# EIB32-JAE-HPC-v1.net
KiCad netlist of a schematic drawn in EAGLE
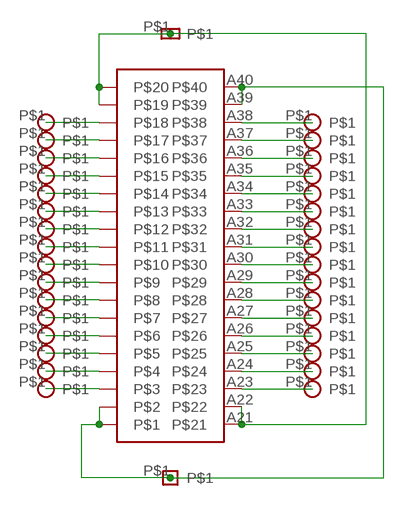
[diagram p0: schematic, sheet 1]

(export (version "E")
  (design (tool "Eeschema 10.0.6"))
  (components
    (comp (ref "U$1")
      (value "WR-40SB-VFH30")
      (footprint "eagle-import:WR-40SB-VFH30")
      (libsource (lib "eagle-import") (part "WR-40SB-VFH30"))
    )
    (comp (ref "U$2")
      (value "EIB-GND-HOLE-PAD-SMALL")
      (footprint "eagle-import:EIB-GND-HOLE-PAD-SMALL")
      (libsource (lib "eagle-import") (part "EIB-GND-HOLE-PAD-SMALL"))
    )
    (comp (ref "U$3")
      (value "EIB-GND-HOLE-PAD")
      (footprint "eagle-import:EIB-GND-HOLE-PAD")
      (libsource (lib "eagle-import") (part "EIB-GND-HOLE-PAD"))
    )
    (comp (ref "U$5")
      (value "EIB-TETRODE-HOLE-RS-PAD")
      (footprint "eagle-import:EIB-TETRODE-HOLE-RS-PAD")
      (libsource (lib "eagle-import") (part "EIB-TETRODE-HOLE-RS-PAD"))
    )
    (comp (ref "U$6")
      (value "EIB-TETRODE-HOLE-RS-PAD")
      (footprint "eagle-import:EIB-TETRODE-HOLE-RS-PAD")
      (libsource (lib "eagle-import") (part "EIB-TETRODE-HOLE-RS-PAD"))
    )
    (comp (ref "U$7")
      (value "EIB-TETRODE-HOLE-RS-PAD")
      (footprint "eagle-import:EIB-TETRODE-HOLE-RS-PAD")
      (libsource (lib "eagle-import") (part "EIB-TETRODE-HOLE-RS-PAD"))
    )
    (comp (ref "U$8")
      (value "EIB-TETRODE-HOLE-RS-PAD")
      (footprint "eagle-import:EIB-TETRODE-HOLE-RS-PAD")
      (libsource (lib "eagle-import") (part "EIB-TETRODE-HOLE-RS-PAD"))
    )
    (comp (ref "U$9")
      (value "EIB-TETRODE-HOLE-RS-PAD")
      (footprint "eagle-import:EIB-TETRODE-HOLE-RS-PAD")
      (libsource (lib "eagle-import") (part "EIB-TETRODE-HOLE-RS-PAD"))
    )
    (comp (ref "U$10")
      (value "EIB-TETRODE-HOLE-RS-PAD")
      (footprint "eagle-import:EIB-TETRODE-HOLE-RS-PAD")
      (libsource (lib "eagle-import") (part "EIB-TETRODE-HOLE-RS-PAD"))
    )
    (comp (ref "U$11")
      (value "EIB-TETRODE-HOLE-RS-PAD")
      (footprint "eagle-import:EIB-TETRODE-HOLE-RS-PAD")
      (libsource (lib "eagle-import") (part "EIB-TETRODE-HOLE-RS-PAD"))
    )
    (comp (ref "U$12")
      (value "EIB-TETRODE-HOLE-RS-PAD")
      (footprint "eagle-import:EIB-TETRODE-HOLE-RS-PAD")
      (libsource (lib "eagle-import") (part "EIB-TETRODE-HOLE-RS-PAD"))
    )
    (comp (ref "U$13")
      (value "EIB-TETRODE-HOLE-RS-PAD")
      (footprint "eagle-import:EIB-TETRODE-HOLE-RS-PAD")
      (libsource (lib "eagle-import") (part "EIB-TETRODE-HOLE-RS-PAD"))
    )
    (comp (ref "U$14")
      (value "EIB-TETRODE-HOLE-RS-PAD")
      (footprint "eagle-import:EIB-TETRODE-HOLE-RS-PAD")
      (libsource (lib "eagle-import") (part "EIB-TETRODE-HOLE-RS-PAD"))
    )
    (comp (ref "U$15")
      (value "EIB-TETRODE-HOLE-RS-PAD")
      (footprint "eagle-import:EIB-TETRODE-HOLE-RS-PAD")
      (libsource (lib "eagle-import") (part "EIB-TETRODE-HOLE-RS-PAD"))
    )
    (comp (ref "U$16")
      (value "EIB-TETRODE-HOLE-RS-PAD")
      (footprint "eagle-import:EIB-TETRODE-HOLE-RS-PAD")
      (libsource (lib "eagle-import") (part "EIB-TETRODE-HOLE-RS-PAD"))
    )
    (comp (ref "U$17")
      (value "EIB-TETRODE-HOLE-RS-PAD")
      (footprint "eagle-import:EIB-TETRODE-HOLE-RS-PAD")
      (libsource (lib "eagle-import") (part "EIB-TETRODE-HOLE-RS-PAD"))
    )
    (comp (ref "U$18")
      (value "EIB-TETRODE-HOLE-RS-PAD")
      (footprint "eagle-import:EIB-TETRODE-HOLE-RS-PAD")
      (libsource (lib "eagle-import") (part "EIB-TETRODE-HOLE-RS-PAD"))
    )
    (comp (ref "U$19")
      (value "EIB-TETRODE-HOLE-RS-PAD")
      (footprint "eagle-import:EIB-TETRODE-HOLE-RS-PAD")
      (libsource (lib "eagle-import") (part "EIB-TETRODE-HOLE-RS-PAD"))
    )
    (comp (ref "U$20")
      (value "EIB-TETRODE-HOLE-RS-PAD")
      (footprint "eagle-import:EIB-TETRODE-HOLE-RS-PAD")
      (libsource (lib "eagle-import") (part "EIB-TETRODE-HOLE-RS-PAD"))
    )
    (comp (ref "U$23")
      (value "EIB-TETRODE-HOLE-RS-PAD")
      (footprint "eagle-import:EIB-TETRODE-HOLE-RS-PAD")
      (libsource (lib "eagle-import") (part "EIB-TETRODE-HOLE-RS-PAD"))
    )
    (comp (ref "U$24")
      (value "EIB-TETRODE-HOLE-RS-PAD")
      (footprint "eagle-import:EIB-TETRODE-HOLE-RS-PAD")
      (libsource (lib "eagle-import") (part "EIB-TETRODE-HOLE-RS-PAD"))
    )
    (comp (ref "U$25")
      (value "EIB-TETRODE-HOLE-RS-PAD")
      (footprint "eagle-import:EIB-TETRODE-HOLE-RS-PAD")
      (libsource (lib "eagle-import") (part "EIB-TETRODE-HOLE-RS-PAD"))
    )
    (comp (ref "U$26")
      (value "EIB-TETRODE-HOLE-RS-PAD")
      (footprint "eagle-import:EIB-TETRODE-HOLE-RS-PAD")
      (libsource (lib "eagle-import") (part "EIB-TETRODE-HOLE-RS-PAD"))
    )
    (comp (ref "U$27")
      (value "EIB-TETRODE-HOLE-RS-PAD")
      (footprint "eagle-import:EIB-TETRODE-HOLE-RS-PAD")
      (libsource (lib "eagle-import") (part "EIB-TETRODE-HOLE-RS-PAD"))
    )
    (comp (ref "U$28")
      (value "EIB-TETRODE-HOLE-RS-PAD")
      (footprint "eagle-import:EIB-TETRODE-HOLE-RS-PAD")
      (libsource (lib "eagle-import") (part "EIB-TETRODE-HOLE-RS-PAD"))
    )
    (comp (ref "U$29")
      (value "EIB-TETRODE-HOLE-RS-PAD")
      (footprint "eagle-import:EIB-TETRODE-HOLE-RS-PAD")
      (libsource (lib "eagle-import") (part "EIB-TETRODE-HOLE-RS-PAD"))
    )
    (comp (ref "U$30")
      (value "EIB-TETRODE-HOLE-RS-PAD")
      (footprint "eagle-import:EIB-TETRODE-HOLE-RS-PAD")
      (libsource (lib "eagle-import") (part "EIB-TETRODE-HOLE-RS-PAD"))
    )
    (comp (ref "U$31")
      (value "EIB-TETRODE-HOLE-RS-PAD")
      (footprint "eagle-import:EIB-TETRODE-HOLE-RS-PAD")
      (libsource (lib "eagle-import") (part "EIB-TETRODE-HOLE-RS-PAD"))
    )
    (comp (ref "U$32")
      (value "EIB-TETRODE-HOLE-RS-PAD")
      (footprint "eagle-import:EIB-TETRODE-HOLE-RS-PAD")
      (libsource (lib "eagle-import") (part "EIB-TETRODE-HOLE-RS-PAD"))
    )
    (comp (ref "U$33")
      (value "EIB-TETRODE-HOLE-RS-PAD")
      (footprint "eagle-import:EIB-TETRODE-HOLE-RS-PAD")
      (libsource (lib "eagle-import") (part "EIB-TETRODE-HOLE-RS-PAD"))
    )
    (comp (ref "U$34")
      (value "EIB-TETRODE-HOLE-RS-PAD")
      (footprint "eagle-import:EIB-TETRODE-HOLE-RS-PAD")
      (libsource (lib "eagle-import") (part "EIB-TETRODE-HOLE-RS-PAD"))
    )
    (comp (ref "U$35")
      (value "EIB-TETRODE-HOLE-RS-PAD")
      (footprint "eagle-import:EIB-TETRODE-HOLE-RS-PAD")
      (libsource (lib "eagle-import") (part "EIB-TETRODE-HOLE-RS-PAD"))
    )
    (comp (ref "U$36")
      (value "EIB-TETRODE-HOLE-RS-PAD")
      (footprint "eagle-import:EIB-TETRODE-HOLE-RS-PAD")
      (libsource (lib "eagle-import") (part "EIB-TETRODE-HOLE-RS-PAD"))
    )
    (comp (ref "U$37")
      (value "EIB-TETRODE-HOLE-RS-PAD")
      (footprint "eagle-import:EIB-TETRODE-HOLE-RS-PAD")
      (libsource (lib "eagle-import") (part "EIB-TETRODE-HOLE-RS-PAD"))
    )
    (comp (ref "U$38")
      (value "EIB-TETRODE-HOLE-RS-PAD")
      (footprint "eagle-import:EIB-TETRODE-HOLE-RS-PAD")
      (libsource (lib "eagle-import") (part "EIB-TETRODE-HOLE-RS-PAD"))
    )
  )
  (nets
    (net (code "1") (name "Net-(U$1-P$1)") (class "Default")
      (node (ref "U$1") (pin "A1") (pinfunction "P$1_A1") (pintype "bidirectional"))
      (node (ref "U$1") (pin "A2") (pinfunction "P$2_A2") (pintype "bidirectional"))
      (node (ref "U$1") (pin "A39") (pinfunction "P$39_A39") (pintype "bidirectional"))
      (node (ref "U$1") (pin "A40") (pinfunction "P$40_A40") (pintype "bidirectional"))
      (node (ref "U$3") (pin "P$1") (pinfunction "P$1_P$1") (pintype "bidirectional"))
    )
    (net (code "2") (name "Net-(U$1-P$3)") (class "Default")
      (node (ref "U$1") (pin "A3") (pinfunction "P$3_A3") (pintype "bidirectional"))
      (node (ref "U$20") (pin "P$1") (pinfunction "P$1_P$1") (pintype "bidirectional"))
    )
    (net (code "3") (name "Net-(U$1-P$4)") (class "Default")
      (node (ref "U$1") (pin "A4") (pinfunction "P$4_A4") (pintype "bidirectional"))
      (node (ref "U$19") (pin "P$1") (pinfunction "P$1_P$1") (pintype "bidirectional"))
    )
    (net (code "4") (name "Net-(U$1-P$5)") (class "Default")
      (node (ref "U$1") (pin "A5") (pinfunction "P$5_A5") (pintype "bidirectional"))
      (node (ref "U$18") (pin "P$1") (pinfunction "P$1_P$1") (pintype "bidirectional"))
    )
    (net (code "5") (name "Net-(U$1-P$6)") (class "Default")
      (node (ref "U$1") (pin "A6") (pinfunction "P$6_A6") (pintype "bidirectional"))
      (node (ref "U$17") (pin "P$1") (pinfunction "P$1_P$1") (pintype "bidirectional"))
    )
    (net (code "6") (name "Net-(U$1-P$7)") (class "Default")
      (node (ref "U$1") (pin "A7") (pinfunction "P$7_A7") (pintype "bidirectional"))
      (node (ref "U$16") (pin "P$1") (pinfunction "P$1_P$1") (pintype "bidirectional"))
    )
    (net (code "7") (name "Net-(U$1-P$8)") (class "Default")
      (node (ref "U$1") (pin "A8") (pinfunction "P$8_A8") (pintype "bidirectional"))
      (node (ref "U$15") (pin "P$1") (pinfunction "P$1_P$1") (pintype "bidirectional"))
    )
    (net (code "8") (name "Net-(U$1-P$9)") (class "Default")
      (node (ref "U$1") (pin "A9") (pinfunction "P$9_A9") (pintype "bidirectional"))
      (node (ref "U$14") (pin "P$1") (pinfunction "P$1_P$1") (pintype "bidirectional"))
    )
    (net (code "9") (name "Net-(U$1-P$10)") (class "Default")
      (node (ref "U$1") (pin "A10") (pinfunction "P$10_A10") (pintype "bidirectional"))
      (node (ref "U$13") (pin "P$1") (pinfunction "P$1_P$1") (pintype "bidirectional"))
    )
    (net (code "10") (name "Net-(U$1-P$11)") (class "Default")
      (node (ref "U$1") (pin "A11") (pinfunction "P$11_A11") (pintype "bidirectional"))
      (node (ref "U$12") (pin "P$1") (pinfunction "P$1_P$1") (pintype "bidirectional"))
    )
    (net (code "11") (name "Net-(U$1-P$12)") (class "Default")
      (node (ref "U$1") (pin "A12") (pinfunction "P$12_A12") (pintype "bidirectional"))
      (node (ref "U$11") (pin "P$1") (pinfunction "P$1_P$1") (pintype "bidirectional"))
    )
    (net (code "12") (name "Net-(U$1-P$13)") (class "Default")
      (node (ref "U$1") (pin "A13") (pinfunction "P$13_A13") (pintype "bidirectional"))
      (node (ref "U$10") (pin "P$1") (pinfunction "P$1_P$1") (pintype "bidirectional"))
    )
    (net (code "13") (name "Net-(U$1-P$14)") (class "Default")
      (node (ref "U$1") (pin "A14") (pinfunction "P$14_A14") (pintype "bidirectional"))
      (node (ref "U$9") (pin "P$1") (pinfunction "P$1_P$1") (pintype "bidirectional"))
    )
    (net (code "14") (name "Net-(U$1-P$15)") (class "Default")
      (node (ref "U$1") (pin "A15") (pinfunction "P$15_A15") (pintype "bidirectional"))
      (node (ref "U$8") (pin "P$1") (pinfunction "P$1_P$1") (pintype "bidirectional"))
    )
    (net (code "15") (name "Net-(U$1-P$16)") (class "Default")
      (node (ref "U$1") (pin "A16") (pinfunction "P$16_A16") (pintype "bidirectional"))
      (node (ref "U$7") (pin "P$1") (pinfunction "P$1_P$1") (pintype "bidirectional"))
    )
    (net (code "16") (name "Net-(U$1-P$17)") (class "Default")
      (node (ref "U$1") (pin "A17") (pinfunction "P$17_A17") (pintype "bidirectional"))
      (node (ref "U$6") (pin "P$1") (pinfunction "P$1_P$1") (pintype "bidirectional"))
    )
    (net (code "17") (name "Net-(U$1-P$18)") (class "Default")
      (node (ref "U$1") (pin "A18") (pinfunction "P$18_A18") (pintype "bidirectional"))
      (node (ref "U$5") (pin "P$1") (pinfunction "P$1_P$1") (pintype "bidirectional"))
    )
    (net (code "18") (name "Net-(U$1-P$19)") (class "Default")
      (node (ref "U$1") (pin "A19") (pinfunction "P$19_A19") (pintype "bidirectional"))
      (node (ref "U$1") (pin "A20") (pinfunction "P$20_A20") (pintype "bidirectional"))
      (node (ref "U$1") (pin "A21") (pinfunction "P$21_A21") (pintype "bidirectional"))
      (node (ref "U$1") (pin "A22") (pinfunction "P$22_A22") (pintype "bidirectional"))
      (node (ref "U$2") (pin "P$1") (pinfunction "P$1_P$1") (pintype "bidirectional"))
    )
    (net (code "19") (name "Net-(U$1-P$23)") (class "Default")
      (node (ref "U$1") (pin "A23") (pinfunction "P$23_A23") (pintype "bidirectional"))
      (node (ref "U$38") (pin "P$1") (pinfunction "P$1_P$1") (pintype "bidirectional"))
    )
    (net (code "20") (name "Net-(U$1-P$24)") (class "Default")
      (node (ref "U$1") (pin "A24") (pinfunction "P$24_A24") (pintype "bidirectional"))
      (node (ref "U$37") (pin "P$1") (pinfunction "P$1_P$1") (pintype "bidirectional"))
    )
    (net (code "21") (name "Net-(U$1-P$25)") (class "Default")
      (node (ref "U$1") (pin "A25") (pinfunction "P$25_A25") (pintype "bidirectional"))
      (node (ref "U$36") (pin "P$1") (pinfunction "P$1_P$1") (pintype "bidirectional"))
    )
    (net (code "22") (name "Net-(U$1-P$26)") (class "Default")
      (node (ref "U$1") (pin "A26") (pinfunction "P$26_A26") (pintype "bidirectional"))
      (node (ref "U$35") (pin "P$1") (pinfunction "P$1_P$1") (pintype "bidirectional"))
    )
    (net (code "23") (name "Net-(U$1-P$27)") (class "Default")
      (node (ref "U$1") (pin "A27") (pinfunction "P$27_A27") (pintype "bidirectional"))
      (node (ref "U$34") (pin "P$1") (pinfunction "P$1_P$1") (pintype "bidirectional"))
    )
    (net (code "24") (name "Net-(U$1-P$28)") (class "Default")
      (node (ref "U$1") (pin "A28") (pinfunction "P$28_A28") (pintype "bidirectional"))
      (node (ref "U$33") (pin "P$1") (pinfunction "P$1_P$1") (pintype "bidirectional"))
    )
    (net (code "25") (name "Net-(U$1-P$29)") (class "Default")
      (node (ref "U$1") (pin "A29") (pinfunction "P$29_A29") (pintype "bidirectional"))
      (node (ref "U$32") (pin "P$1") (pinfunction "P$1_P$1") (pintype "bidirectional"))
    )
    (net (code "26") (name "Net-(U$1-P$30)") (class "Default")
      (node (ref "U$1") (pin "A30") (pinfunction "P$30_A30") (pintype "bidirectional"))
      (node (ref "U$31") (pin "P$1") (pinfunction "P$1_P$1") (pintype "bidirectional"))
    )
    (net (code "27") (name "Net-(U$1-P$31)") (class "Default")
      (node (ref "U$1") (pin "A31") (pinfunction "P$31_A31") (pintype "bidirectional"))
      (node (ref "U$30") (pin "P$1") (pinfunction "P$1_P$1") (pintype "bidirectional"))
    )
    (net (code "28") (name "Net-(U$1-P$32)") (class "Default")
      (node (ref "U$1") (pin "A32") (pinfunction "P$32_A32") (pintype "bidirectional"))
      (node (ref "U$29") (pin "P$1") (pinfunction "P$1_P$1") (pintype "bidirectional"))
    )
    (net (code "29") (name "Net-(U$1-P$33)") (class "Default")
      (node (ref "U$1") (pin "A33") (pinfunction "P$33_A33") (pintype "bidirectional"))
      (node (ref "U$28") (pin "P$1") (pinfunction "P$1_P$1") (pintype "bidirectional"))
    )
    (net (code "30") (name "Net-(U$1-P$34)") (class "Default")
      (node (ref "U$1") (pin "A34") (pinfunction "P$34_A34") (pintype "bidirectional"))
      (node (ref "U$27") (pin "P$1") (pinfunction "P$1_P$1") (pintype "bidirectional"))
    )
    (net (code "31") (name "Net-(U$1-P$35)") (class "Default")
      (node (ref "U$1") (pin "A35") (pinfunction "P$35_A35") (pintype "bidirectional"))
      (node (ref "U$26") (pin "P$1") (pinfunction "P$1_P$1") (pintype "bidirectional"))
    )
    (net (code "32") (name "Net-(U$1-P$36)") (class "Default")
      (node (ref "U$1") (pin "A36") (pinfunction "P$36_A36") (pintype "bidirectional"))
      (node (ref "U$25") (pin "P$1") (pinfunction "P$1_P$1") (pintype "bidirectional"))
    )
    (net (code "33") (name "Net-(U$1-P$37)") (class "Default")
      (node (ref "U$1") (pin "A37") (pinfunction "P$37_A37") (pintype "bidirectional"))
      (node (ref "U$24") (pin "P$1") (pinfunction "P$1_P$1") (pintype "bidirectional"))
    )
    (net (code "34") (name "Net-(U$1-P$38)") (class "Default")
      (node (ref "U$1") (pin "A38") (pinfunction "P$38_A38") (pintype "bidirectional"))
      (node (ref "U$23") (pin "P$1") (pinfunction "P$1_P$1") (pintype "bidirectional"))
    )
  )
)
